# Tetris.net
KiCad netlist of a schematic drawn in EAGLE
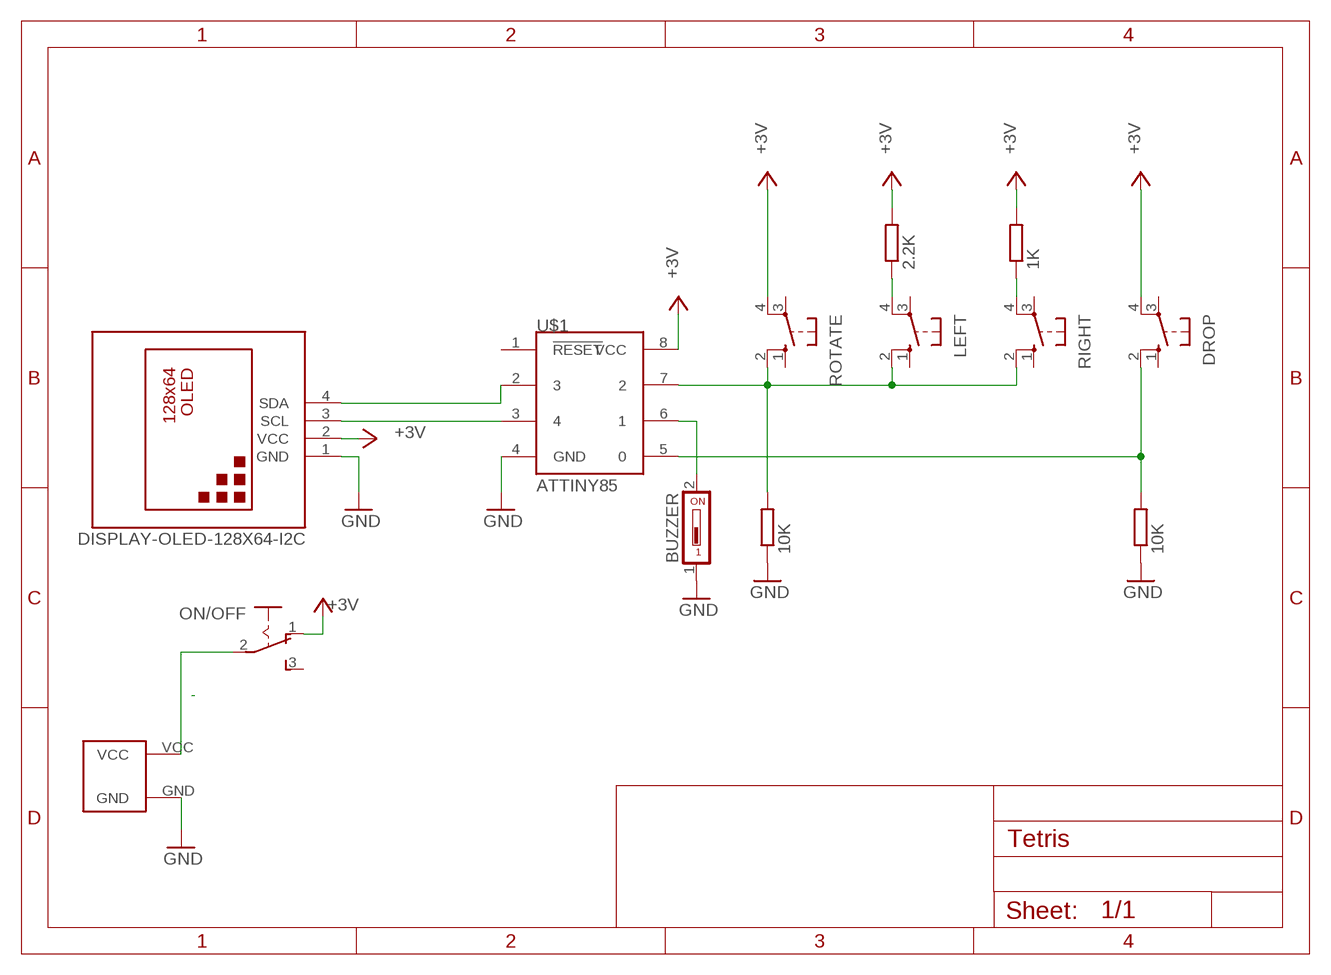
[diagram p0: schematic, sheet 1]

(export (version "E")
  (design (tool "Eeschema 10.0.6"))
  (components
    (comp (ref "BUZZER")
      (value "DS01")
      (footprint "eagle-import:DS-01")
      (libsource (lib "eagle-import") (part "DS01"))
    )
    (comp (ref "DROP")
      (value "10-XX")
      (footprint "eagle-import:B3F-10XX")
      (fields (field (name "MPN") "B3F-1000"))
      (libsource (lib "eagle-import") (part "10-XX"))
    )
    (comp (ref "LEFT")
      (value "10-XX")
      (footprint "eagle-import:B3F-10XX")
      (fields (field (name "MPN") "B3F-1000"))
      (libsource (lib "eagle-import") (part "10-XX"))
    )
    (comp (ref "ON/OFF")
      (value "M251")
      (footprint "eagle-import:M251")
      (libsource (lib "eagle-import") (part "M251"))
    )
    (comp (ref "R1")
      (value "2.2K")
      (footprint "eagle-import:0207_10")
      (libsource (lib "eagle-import") (part "R-EU_0207/10"))
    )
    (comp (ref "R2")
      (value "10K")
      (footprint "eagle-import:0207_10")
      (libsource (lib "eagle-import") (part "R-EU_0207/10"))
    )
    (comp (ref "R3")
      (value "1K")
      (footprint "eagle-import:0207_10")
      (libsource (lib "eagle-import") (part "R-EU_0207/10"))
    )
    (comp (ref "R4")
      (value "10K")
      (footprint "eagle-import:0207_10")
      (libsource (lib "eagle-import") (part "R-EU_0207/10"))
    )
    (comp (ref "RIGHT")
      (value "10-XX")
      (footprint "eagle-import:B3F-10XX")
      (fields (field (name "MPN") "B3F-1000"))
      (libsource (lib "eagle-import") (part "10-XX"))
    )
    (comp (ref "ROTATE")
      (value "10-XX")
      (footprint "eagle-import:B3F-10XX")
      (fields (field (name "MPN") "B3F-1000"))
      (libsource (lib "eagle-import") (part "10-XX"))
    )
    (comp (ref "U$1")
      (value "ATTINY85")
      (footprint "eagle-import:8P3")
      (libsource (lib "eagle-import") (part "ATTINY85"))
    )
    (comp (ref "U$2")
      (value "DISPLAY-OLED-128X64-I2C")
      (footprint "eagle-import:DISPLAY-OLED-128X64-I2C")
      (libsource (lib "eagle-import") (part "DISPLAY-OLED-128X64-I2C"))
    )
    (comp (ref "U$5")
      (value "CR2032")
      (footprint "eagle-import:CR2032-20MM")
      (libsource (lib "eagle-import") (part "CR2032"))
    )
  )
  (nets
    (net (code "1") (name "+3V") (class "Default")
      (node (ref "DROP") (pin "4") (pinfunction "P1_4") (pintype "passive"))
      (node (ref "ON/OFF") (pin "1") (pinfunction "O_1") (pintype "passive"))
      (node (ref "R1") (pin "2") (pinfunction "2_2") (pintype "passive"))
      (node (ref "R3") (pin "2") (pinfunction "2_2") (pintype "passive"))
      (node (ref "ROTATE") (pin "4") (pinfunction "P1_4") (pintype "passive"))
      (node (ref "U$1") (pin "8") (pinfunction "VCC_8") (pintype "power_in"))
      (node (ref "U$2") (pin "2") (pinfunction "VCC_2") (pintype "power_in"))
    )
    (net (code "2") (name "GND") (class "Default")
      (node (ref "BUZZER") (pin "1") (pinfunction "1_1") (pintype "passive"))
      (node (ref "R2") (pin "1") (pinfunction "1_1") (pintype "passive"))
      (node (ref "R4") (pin "1") (pinfunction "1_1") (pintype "passive"))
      (node (ref "U$1") (pin "4") (pinfunction "GND_4") (pintype "power_in"))
      (node (ref "U$2") (pin "1") (pinfunction "GND_1") (pintype "power_in"))
      (node (ref "U$5") (pin "GND") (pinfunction "GND_GND") (pintype "bidirectional"))
    )
    (net (code "3") (name "Net-(DROP-S1)") (class "Default")
      (node (ref "DROP") (pin "2") (pinfunction "S1_2") (pintype "passive"))
      (node (ref "R2") (pin "2") (pinfunction "2_2") (pintype "passive"))
      (node (ref "U$1") (pin "5") (pinfunction "0_5") (pintype "bidirectional"))
    )
    (net (code "4") (name "Net-(LEFT-P1)") (class "Default")
      (node (ref "LEFT") (pin "4") (pinfunction "P1_4") (pintype "passive"))
      (node (ref "R1") (pin "1") (pinfunction "1_1") (pintype "passive"))
    )
    (net (code "5") (name "Net-(LEFT-S1)") (class "Default")
      (node (ref "LEFT") (pin "2") (pinfunction "S1_2") (pintype "passive"))
      (node (ref "R4") (pin "2") (pinfunction "2_2") (pintype "passive"))
      (node (ref "RIGHT") (pin "2") (pinfunction "S1_2") (pintype "passive"))
      (node (ref "ROTATE") (pin "2") (pinfunction "S1_2") (pintype "passive"))
      (node (ref "U$1") (pin "7") (pinfunction "2_7") (pintype "bidirectional"))
    )
    (net (code "6") (name "Net-(ON/OFF-P)") (class "Default")
      (node (ref "ON/OFF") (pin "2") (pinfunction "P_2") (pintype "passive"))
      (node (ref "U$5") (pin "VCC") (pinfunction "VCC_VCC") (pintype "bidirectional"))
    )
    (net (code "7") (name "Net-(RIGHT-P1)") (class "Default")
      (node (ref "R3") (pin "1") (pinfunction "1_1") (pintype "passive"))
      (node (ref "RIGHT") (pin "4") (pinfunction "P1_4") (pintype "passive"))
    )
    (net (code "8") (name "Net-(U$1-1)") (class "Default")
      (node (ref "BUZZER") (pin "2") (pinfunction "2_2") (pintype "passive"))
      (node (ref "U$1") (pin "6") (pinfunction "1_6") (pintype "bidirectional"))
    )
    (net (code "9") (name "Net-(U$1-3)") (class "Default")
      (node (ref "U$1") (pin "2") (pinfunction "3_2") (pintype "bidirectional"))
      (node (ref "U$2") (pin "4") (pinfunction "SDA_4") (pintype "bidirectional"))
    )
    (net (code "10") (name "Net-(U$1-4)") (class "Default")
      (node (ref "U$1") (pin "3") (pinfunction "4_3") (pintype "bidirectional"))
      (node (ref "U$2") (pin "3") (pinfunction "SCL_3") (pintype "bidirectional"))
    )
    (net (code "11") (name "unconnected-(DROP-P-Pad3)") (class "Default")
      (node (ref "DROP") (pin "3") (pinfunction "P_3") (pintype "passive"))
    )
    (net (code "12") (name "unconnected-(DROP-S-Pad1)") (class "Default")
      (node (ref "DROP") (pin "1") (pinfunction "S_1") (pintype "passive"))
    )
    (net (code "13") (name "unconnected-(LEFT-P-Pad3)") (class "Default")
      (node (ref "LEFT") (pin "3") (pinfunction "P_3") (pintype "passive"))
    )
    (net (code "14") (name "unconnected-(LEFT-S-Pad1)") (class "Default")
      (node (ref "LEFT") (pin "1") (pinfunction "S_1") (pintype "passive"))
    )
    (net (code "15") (name "unconnected-(ON/OFF-S-Pad3)") (class "Default")
      (node (ref "ON/OFF") (pin "3") (pinfunction "S_3") (pintype "passive"))
    )
    (net (code "16") (name "unconnected-(RIGHT-P-Pad3)") (class "Default")
      (node (ref "RIGHT") (pin "3") (pinfunction "P_3") (pintype "passive"))
    )
    (net (code "17") (name "unconnected-(RIGHT-S-Pad1)") (class "Default")
      (node (ref "RIGHT") (pin "1") (pinfunction "S_1") (pintype "passive"))
    )
    (net (code "18") (name "unconnected-(ROTATE-P-Pad3)") (class "Default")
      (node (ref "ROTATE") (pin "3") (pinfunction "P_3") (pintype "passive"))
    )
    (net (code "19") (name "unconnected-(ROTATE-S-Pad1)") (class "Default")
      (node (ref "ROTATE") (pin "1") (pinfunction "S_1") (pintype "passive"))
    )
    (net (code "20") (name "unconnected-(U$1-~{RESET}-Pad1)") (class "Default")
      (node (ref "U$1") (pin "1") (pinfunction "~{RESET}_1") (pintype "bidirectional"))
    )
  )
)
